# Master.net
KiCad netlist of a schematic drawn in Altium Designer
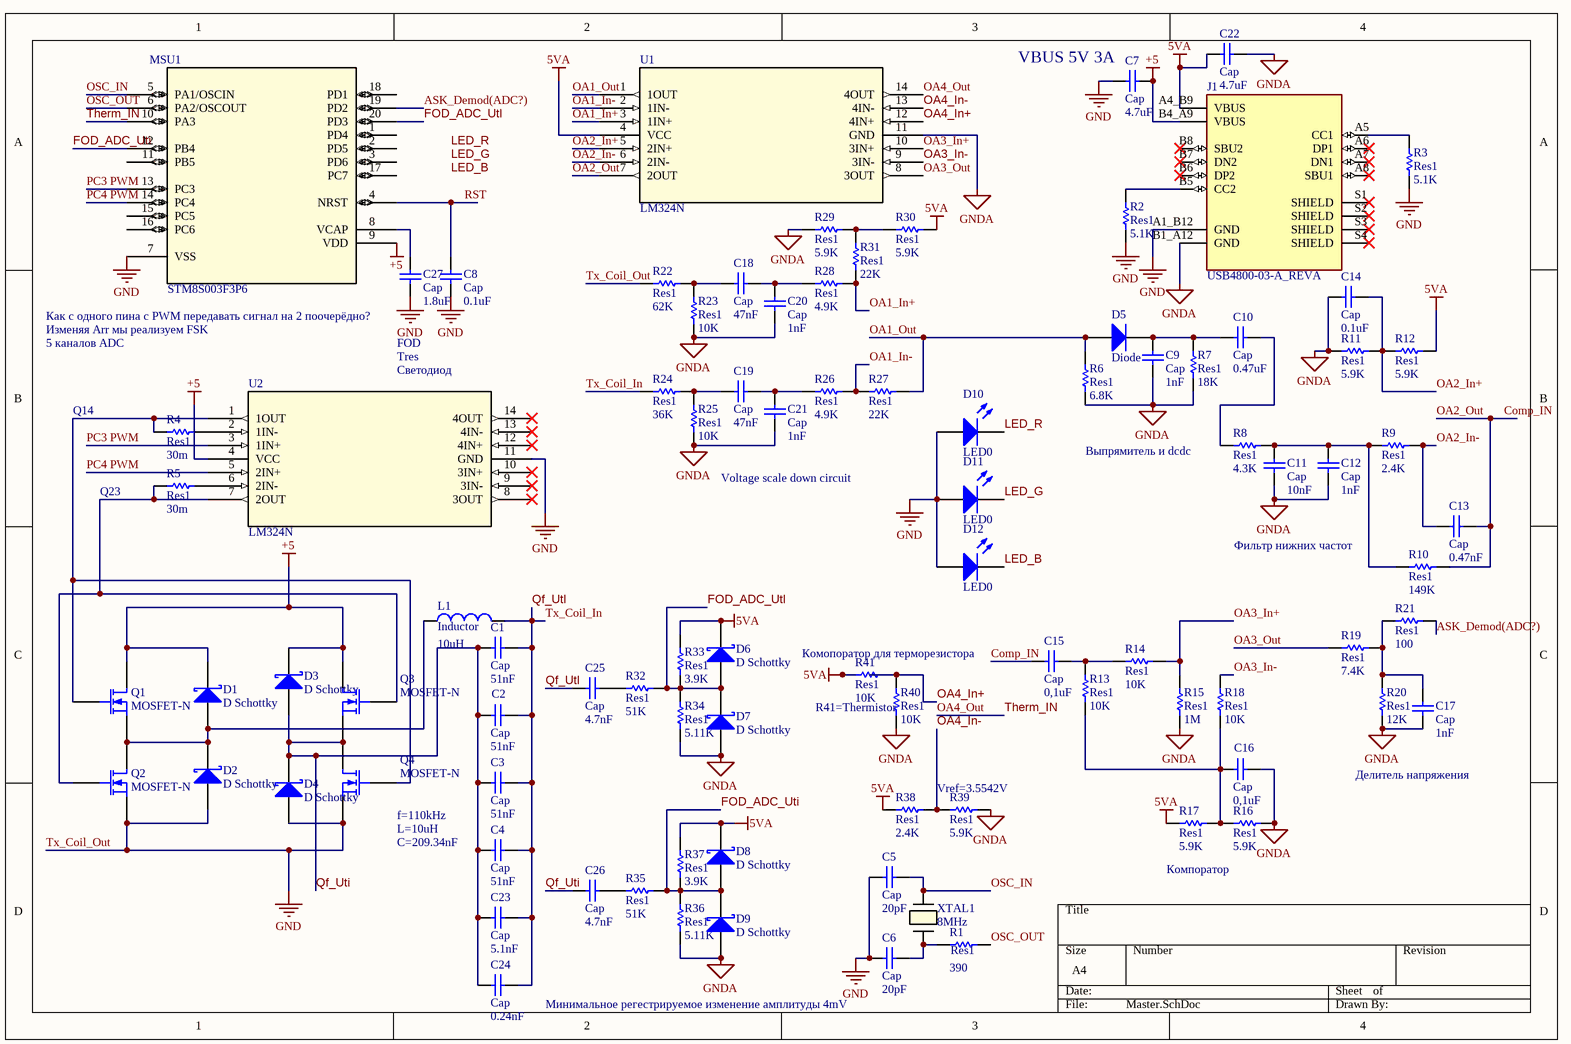
[diagram p0: Master.SchDoc]

(export (version "E")
  (design (tool "Eeschema 10.0.6"))
  (components
    (comp (ref "C1")
      (value "Cap")
      (footprint "RAD-0.3")
      (description "Capacitor")
      (fields (field (name "ALTIUM_VALUE") "51nF") (field (name "PUBLISHER") "Altium Limited"))
      (libsource (lib "Miscellaneous Devices") (part "Cap"))
    )
    (comp (ref "C2")
      (value "Cap")
      (footprint "RAD-0.3")
      (description "Capacitor")
      (fields (field (name "ALTIUM_VALUE") "51nF") (field (name "PUBLISHER") "Altium Limited"))
      (libsource (lib "Miscellaneous Devices") (part "Cap"))
    )
    (comp (ref "C3")
      (value "Cap")
      (footprint "RAD-0.3")
      (description "Capacitor")
      (fields (field (name "ALTIUM_VALUE") "51nF") (field (name "PUBLISHER") "Altium Limited"))
      (libsource (lib "Miscellaneous Devices") (part "Cap"))
    )
    (comp (ref "C4")
      (value "Cap")
      (footprint "RAD-0.3")
      (description "Capacitor")
      (fields (field (name "ALTIUM_VALUE") "51nF") (field (name "PUBLISHER") "Altium Limited"))
      (libsource (lib "Miscellaneous Devices") (part "Cap"))
    )
    (comp (ref "C5")
      (value "Cap")
      (footprint "RAD-0.3")
      (description "Capacitor")
      (fields (field (name "ALTIUM_VALUE") "20pF") (field (name "PUBLISHER") "Altium Limited"))
      (libsource (lib "Miscellaneous Devices") (part "Cap"))
    )
    (comp (ref "C6")
      (value "Cap")
      (footprint "RAD-0.3")
      (description "Capacitor")
      (fields (field (name "ALTIUM_VALUE") "20pF") (field (name "PUBLISHER") "Altium Limited"))
      (libsource (lib "Miscellaneous Devices") (part "Cap"))
    )
    (comp (ref "C7")
      (value "Cap")
      (footprint "RAD-0.3")
      (description "Capacitor")
      (fields (field (name "ALTIUM_VALUE") "4.7uF") (field (name "PUBLISHER") "Altium Limited"))
      (libsource (lib "Miscellaneous Devices") (part "Cap"))
    )
    (comp (ref "C8")
      (value "Cap")
      (footprint "RAD-0.3")
      (description "Capacitor")
      (fields (field (name "ALTIUM_VALUE") "0.1uF") (field (name "PUBLISHER") "Altium Limited"))
      (libsource (lib "Miscellaneous Devices") (part "Cap"))
    )
    (comp (ref "C9")
      (value "Cap")
      (footprint "RAD-0.3")
      (description "Capacitor")
      (fields (field (name "ALTIUM_VALUE") "1nF") (field (name "PUBLISHER") "Altium Limited"))
      (libsource (lib "Miscellaneous Devices") (part "Cap"))
    )
    (comp (ref "C10")
      (value "Cap")
      (footprint "RAD-0.3")
      (description "Capacitor")
      (fields (field (name "ALTIUM_VALUE") "0.47uF") (field (name "PUBLISHER") "Altium Limited"))
      (libsource (lib "Miscellaneous Devices") (part "Cap"))
    )
    (comp (ref "C11")
      (value "Cap")
      (footprint "RAD-0.3")
      (description "Capacitor")
      (fields (field (name "ALTIUM_VALUE") "10nF") (field (name "PUBLISHER") "Altium Limited"))
      (libsource (lib "Miscellaneous Devices") (part "Cap"))
    )
    (comp (ref "C12")
      (value "Cap")
      (footprint "RAD-0.3")
      (description "Capacitor")
      (fields (field (name "ALTIUM_VALUE") "1nF") (field (name "PUBLISHER") "Altium Limited"))
      (libsource (lib "Miscellaneous Devices") (part "Cap"))
    )
    (comp (ref "C13")
      (value "Cap")
      (footprint "RAD-0.3")
      (description "Capacitor")
      (fields (field (name "ALTIUM_VALUE") "0.47nF") (field (name "PUBLISHER") "Altium Limited"))
      (libsource (lib "Miscellaneous Devices") (part "Cap"))
    )
    (comp (ref "C14")
      (value "Cap")
      (footprint "RAD-0.3")
      (description "Capacitor")
      (fields (field (name "ALTIUM_VALUE") "0.1uF") (field (name "PUBLISHER") "Altium Limited"))
      (libsource (lib "Miscellaneous Devices") (part "Cap"))
    )
    (comp (ref "C15")
      (value "Cap")
      (footprint "RAD-0.3")
      (description "Capacitor")
      (fields (field (name "ALTIUM_VALUE") "0,1uF") (field (name "PUBLISHER") "Altium Limited"))
      (libsource (lib "Miscellaneous Devices") (part "Cap"))
    )
    (comp (ref "C16")
      (value "Cap")
      (footprint "RAD-0.3")
      (description "Capacitor")
      (fields (field (name "ALTIUM_VALUE") "0,1uF") (field (name "PUBLISHER") "Altium Limited"))
      (libsource (lib "Miscellaneous Devices") (part "Cap"))
    )
    (comp (ref "C17")
      (value "Cap")
      (footprint "RAD-0.3")
      (description "Capacitor")
      (fields (field (name "ALTIUM_VALUE") "1nF") (field (name "PUBLISHER") "Altium Limited"))
      (libsource (lib "Miscellaneous Devices") (part "Cap"))
    )
    (comp (ref "C18")
      (value "Cap")
      (footprint "RAD-0.3")
      (description "Capacitor")
      (fields (field (name "ALTIUM_VALUE") "47nF") (field (name "PUBLISHER") "Altium Limited"))
      (libsource (lib "Miscellaneous Devices") (part "Cap"))
    )
    (comp (ref "C19")
      (value "Cap")
      (footprint "RAD-0.3")
      (description "Capacitor")
      (fields (field (name "ALTIUM_VALUE") "47nF") (field (name "PUBLISHER") "Altium Limited"))
      (libsource (lib "Miscellaneous Devices") (part "Cap"))
    )
    (comp (ref "C20")
      (value "Cap")
      (footprint "RAD-0.3")
      (description "Capacitor")
      (fields (field (name "ALTIUM_VALUE") "1nF") (field (name "PUBLISHER") "Altium Limited"))
      (libsource (lib "Miscellaneous Devices") (part "Cap"))
    )
    (comp (ref "C21")
      (value "Cap")
      (footprint "RAD-0.3")
      (description "Capacitor")
      (fields (field (name "ALTIUM_VALUE") "1nF") (field (name "PUBLISHER") "Altium Limited"))
      (libsource (lib "Miscellaneous Devices") (part "Cap"))
    )
    (comp (ref "C22")
      (value "Cap")
      (footprint "RAD-0.3")
      (description "Capacitor")
      (fields (field (name "ALTIUM_VALUE") "4.7uF") (field (name "PUBLISHER") "Altium Limited"))
      (libsource (lib "Miscellaneous Devices") (part "Cap"))
    )
    (comp (ref "C23")
      (value "Cap")
      (footprint "RAD-0.3")
      (description "Capacitor")
      (fields (field (name "ALTIUM_VALUE") "5.1nF") (field (name "PUBLISHER") "Altium Limited"))
      (libsource (lib "Miscellaneous Devices") (part "Cap"))
    )
    (comp (ref "C24")
      (value "Cap")
      (footprint "RAD-0.3")
      (description "Capacitor")
      (fields (field (name "ALTIUM_VALUE") "0.24nF") (field (name "PUBLISHER") "Altium Limited"))
      (libsource (lib "Miscellaneous Devices") (part "Cap"))
    )
    (comp (ref "C25")
      (value "Cap")
      (footprint "RAD-0.3")
      (description "Capacitor")
      (fields (field (name "ALTIUM_VALUE") "4.7nF") (field (name "PUBLISHER") "Altium Limited"))
      (libsource (lib "Miscellaneous Devices") (part "Cap"))
    )
    (comp (ref "C26")
      (value "Cap")
      (footprint "RAD-0.3")
      (description "Capacitor")
      (fields (field (name "ALTIUM_VALUE") "4.7nF") (field (name "PUBLISHER") "Altium Limited"))
      (libsource (lib "Miscellaneous Devices") (part "Cap"))
    )
    (comp (ref "C27")
      (value "Cap")
      (footprint "RAD-0.3")
      (description "Capacitor")
      (fields (field (name "ALTIUM_VALUE") "1.8uF") (field (name "PUBLISHER") "Altium Limited"))
      (libsource (lib "Miscellaneous Devices") (part "Cap"))
    )
    (comp (ref "D1")
      (value "D Schottky")
      (footprint "SMB")
      (description "Schottky Diode")
      (fields (field (name "PUBLISHER") "Altium Limited"))
      (libsource (lib "Miscellaneous Devices") (part "D Schottky"))
    )
    (comp (ref "D2")
      (value "D Schottky")
      (footprint "SMB")
      (description "Schottky Diode")
      (fields (field (name "PUBLISHER") "Altium Limited"))
      (libsource (lib "Miscellaneous Devices") (part "D Schottky"))
    )
    (comp (ref "D3")
      (value "D Schottky")
      (footprint "SMB")
      (description "Schottky Diode")
      (fields (field (name "PUBLISHER") "Altium Limited"))
      (libsource (lib "Miscellaneous Devices") (part "D Schottky"))
    )
    (comp (ref "D4")
      (value "D Schottky")
      (footprint "SMB")
      (description "Schottky Diode")
      (fields (field (name "PUBLISHER") "Altium Limited"))
      (libsource (lib "Miscellaneous Devices") (part "D Schottky"))
    )
    (comp (ref "D5")
      (value "Diode")
      (footprint "SMC")
      (description "Default Diode")
      (fields (field (name "PUBLISHER") "Altium Limited"))
      (libsource (lib "Miscellaneous Devices") (part "Diode"))
    )
    (comp (ref "D6")
      (value "D Schottky")
      (footprint "SMB")
      (description "Schottky Diode")
      (fields (field (name "PUBLISHER") "Altium Limited"))
      (libsource (lib "Miscellaneous Devices") (part "D Schottky"))
    )
    (comp (ref "D7")
      (value "D Schottky")
      (footprint "SMB")
      (description "Schottky Diode")
      (fields (field (name "PUBLISHER") "Altium Limited"))
      (libsource (lib "Miscellaneous Devices") (part "D Schottky"))
    )
    (comp (ref "D8")
      (value "D Schottky")
      (footprint "SMB")
      (description "Schottky Diode")
      (fields (field (name "PUBLISHER") "Altium Limited"))
      (libsource (lib "Miscellaneous Devices") (part "D Schottky"))
    )
    (comp (ref "D9")
      (value "D Schottky")
      (footprint "SMB")
      (description "Schottky Diode")
      (fields (field (name "PUBLISHER") "Altium Limited"))
      (libsource (lib "Miscellaneous Devices") (part "D Schottky"))
    )
    (comp (ref "D10")
      (value "LED0")
      (footprint "LED-0")
      (description "Typical INFRARED GaAs LED")
      (fields (field (name "PUBLISHER") "Altium Limited"))
      (libsource (lib "Miscellaneous Devices") (part "LED0"))
    )
    (comp (ref "D11")
      (value "LED0")
      (footprint "LED-0")
      (description "Typical INFRARED GaAs LED")
      (fields (field (name "PUBLISHER") "Altium Limited"))
      (libsource (lib "Miscellaneous Devices") (part "LED0"))
    )
    (comp (ref "D12")
      (value "LED0")
      (footprint "LED-0")
      (description "Typical INFRARED GaAs LED")
      (fields (field (name "PUBLISHER") "Altium Limited"))
      (libsource (lib "Miscellaneous Devices") (part "LED0"))
    )
    (comp (ref "J1")
      (value "USB4800-03-A_REVA")
      (footprint "GCT_USB4800-03-A_REVA")
      (fields (field (name "MP") "USB4800-03-A") (field (name "MF") "Global Connector Technology"))
      (libsource (lib "USB4800-03-A_REVA") (part "USB4800-03-A_REVA"))
    )
    (comp (ref "L1")
      (value "Inductor")
      (footprint "0402-A")
      (fields (field (name "ALTIUM_VALUE") "10uH") (field (name "PUBLISHER") "Altium Limited"))
      (libsource (lib "Miscellaneous Devices") (part "Inductor"))
    )
    (comp (ref "MSU1")
      (value "STM8S003F3P6")
      (footprint "TSSOP20")
      (description "No Description Available")
      (libsource (lib "STM8S003F3P6") (part "STM8S003F3P6"))
    )
    (comp (ref "Q1")
      (value "MOSFET-N")
      (footprint "E3")
      (description "N-Channel MOSFET")
      (fields (field (name "PUBLISHER") "Altium Limited"))
      (libsource (lib "Miscellaneous Devices") (part "MOSFET-N"))
    )
    (comp (ref "Q2")
      (value "MOSFET-N")
      (footprint "E3")
      (description "N-Channel MOSFET")
      (fields (field (name "PUBLISHER") "Altium Limited"))
      (libsource (lib "Miscellaneous Devices") (part "MOSFET-N"))
    )
    (comp (ref "Q3")
      (value "MOSFET-N")
      (footprint "E3")
      (description "N-Channel MOSFET")
      (fields (field (name "PUBLISHER") "Altium Limited"))
      (libsource (lib "Miscellaneous Devices") (part "MOSFET-N"))
    )
    (comp (ref "Q4")
      (value "MOSFET-N")
      (footprint "E3")
      (description "N-Channel MOSFET")
      (fields (field (name "PUBLISHER") "Altium Limited"))
      (libsource (lib "Miscellaneous Devices") (part "MOSFET-N"))
    )
    (comp (ref "R1")
      (value "Res1")
      (footprint "AXIAL-0.3")
      (description "Resistor")
      (fields (field (name "ALTIUM_VALUE") "390") (field (name "PUBLISHER") "Altium Limited"))
      (libsource (lib "Miscellaneous Devices") (part "Res1"))
    )
    (comp (ref "R2")
      (value "Res1")
      (footprint "AXIAL-0.3")
      (description "Resistor")
      (fields (field (name "ALTIUM_VALUE") "5.1K") (field (name "PUBLISHER") "Altium Limited"))
      (libsource (lib "Miscellaneous Devices") (part "Res1"))
    )
    (comp (ref "R3")
      (value "Res1")
      (footprint "AXIAL-0.3")
      (description "Resistor")
      (fields (field (name "ALTIUM_VALUE") "5.1K") (field (name "PUBLISHER") "Altium Limited"))
      (libsource (lib "Miscellaneous Devices") (part "Res1"))
    )
    (comp (ref "R4")
      (value "Res1")
      (footprint "AXIAL-0.3")
      (description "Resistor")
      (fields (field (name "ALTIUM_VALUE") "30m") (field (name "PUBLISHER") "Altium Limited"))
      (libsource (lib "Miscellaneous Devices") (part "Res1"))
    )
    (comp (ref "R5")
      (value "Res1")
      (footprint "AXIAL-0.3")
      (description "Resistor")
      (fields (field (name "ALTIUM_VALUE") "30m") (field (name "PUBLISHER") "Altium Limited"))
      (libsource (lib "Miscellaneous Devices") (part "Res1"))
    )
    (comp (ref "R6")
      (value "Res1")
      (footprint "AXIAL-0.3")
      (description "Resistor")
      (fields (field (name "ALTIUM_VALUE") "6.8K") (field (name "PUBLISHER") "Altium Limited"))
      (libsource (lib "Miscellaneous Devices") (part "Res1"))
    )
    (comp (ref "R7")
      (value "Res1")
      (footprint "AXIAL-0.3")
      (description "Resistor")
      (fields (field (name "ALTIUM_VALUE") "18K") (field (name "PUBLISHER") "Altium Limited"))
      (libsource (lib "Miscellaneous Devices") (part "Res1"))
    )
    (comp (ref "R8")
      (value "Res1")
      (footprint "AXIAL-0.3")
      (description "Resistor")
      (fields (field (name "ALTIUM_VALUE") "4.3K") (field (name "PUBLISHER") "Altium Limited"))
      (libsource (lib "Miscellaneous Devices") (part "Res1"))
    )
    (comp (ref "R9")
      (value "Res1")
      (footprint "AXIAL-0.3")
      (description "Resistor")
      (fields (field (name "ALTIUM_VALUE") "2.4K") (field (name "PUBLISHER") "Altium Limited"))
      (libsource (lib "Miscellaneous Devices") (part "Res1"))
    )
    (comp (ref "R10")
      (value "Res1")
      (footprint "AXIAL-0.3")
      (description "Resistor")
      (fields (field (name "ALTIUM_VALUE") "149K") (field (name "PUBLISHER") "Altium Limited"))
      (libsource (lib "Miscellaneous Devices") (part "Res1"))
    )
    (comp (ref "R11")
      (value "Res1")
      (footprint "AXIAL-0.3")
      (description "Resistor")
      (fields (field (name "ALTIUM_VALUE") "5.9K") (field (name "PUBLISHER") "Altium Limited"))
      (libsource (lib "Miscellaneous Devices") (part "Res1"))
    )
    (comp (ref "R12")
      (value "Res1")
      (footprint "AXIAL-0.3")
      (description "Resistor")
      (fields (field (name "ALTIUM_VALUE") "5.9K") (field (name "PUBLISHER") "Altium Limited"))
      (libsource (lib "Miscellaneous Devices") (part "Res1"))
    )
    (comp (ref "R13")
      (value "Res1")
      (footprint "AXIAL-0.3")
      (description "Resistor")
      (fields (field (name "ALTIUM_VALUE") "10K") (field (name "PUBLISHER") "Altium Limited"))
      (libsource (lib "Miscellaneous Devices") (part "Res1"))
    )
    (comp (ref "R14")
      (value "Res1")
      (footprint "AXIAL-0.3")
      (description "Resistor")
      (fields (field (name "ALTIUM_VALUE") "10K") (field (name "PUBLISHER") "Altium Limited"))
      (libsource (lib "Miscellaneous Devices") (part "Res1"))
    )
    (comp (ref "R15")
      (value "Res1")
      (footprint "AXIAL-0.3")
      (description "Resistor")
      (fields (field (name "ALTIUM_VALUE") "1M") (field (name "PUBLISHER") "Altium Limited"))
      (libsource (lib "Miscellaneous Devices") (part "Res1"))
    )
    (comp (ref "R16")
      (value "Res1")
      (footprint "AXIAL-0.3")
      (description "Resistor")
      (fields (field (name "ALTIUM_VALUE") "5.9K") (field (name "PUBLISHER") "Altium Limited"))
      (libsource (lib "Miscellaneous Devices") (part "Res1"))
    )
    (comp (ref "R17")
      (value "Res1")
      (footprint "AXIAL-0.3")
      (description "Resistor")
      (fields (field (name "ALTIUM_VALUE") "5.9K") (field (name "PUBLISHER") "Altium Limited"))
      (libsource (lib "Miscellaneous Devices") (part "Res1"))
    )
    (comp (ref "R18")
      (value "Res1")
      (footprint "AXIAL-0.3")
      (description "Resistor")
      (fields (field (name "ALTIUM_VALUE") "10K") (field (name "PUBLISHER") "Altium Limited"))
      (libsource (lib "Miscellaneous Devices") (part "Res1"))
    )
    (comp (ref "R19")
      (value "Res1")
      (footprint "AXIAL-0.3")
      (description "Resistor")
      (fields (field (name "ALTIUM_VALUE") "7.4K") (field (name "PUBLISHER") "Altium Limited"))
      (libsource (lib "Miscellaneous Devices") (part "Res1"))
    )
    (comp (ref "R20")
      (value "Res1")
      (footprint "AXIAL-0.3")
      (description "Resistor")
      (fields (field (name "ALTIUM_VALUE") "12K") (field (name "PUBLISHER") "Altium Limited"))
      (libsource (lib "Miscellaneous Devices") (part "Res1"))
    )
    (comp (ref "R21")
      (value "Res1")
      (footprint "AXIAL-0.3")
      (description "Resistor")
      (fields (field (name "ALTIUM_VALUE") "100") (field (name "PUBLISHER") "Altium Limited"))
      (libsource (lib "Miscellaneous Devices") (part "Res1"))
    )
    (comp (ref "R22")
      (value "Res1")
      (footprint "AXIAL-0.3")
      (description "Resistor")
      (fields (field (name "ALTIUM_VALUE") "62K") (field (name "PUBLISHER") "Altium Limited"))
      (libsource (lib "Miscellaneous Devices") (part "Res1"))
    )
    (comp (ref "R23")
      (value "Res1")
      (footprint "AXIAL-0.3")
      (description "Resistor")
      (fields (field (name "ALTIUM_VALUE") "10K") (field (name "PUBLISHER") "Altium Limited"))
      (libsource (lib "Miscellaneous Devices") (part "Res1"))
    )
    (comp (ref "R24")
      (value "Res1")
      (footprint "AXIAL-0.3")
      (description "Resistor")
      (fields (field (name "ALTIUM_VALUE") "36K") (field (name "PUBLISHER") "Altium Limited"))
      (libsource (lib "Miscellaneous Devices") (part "Res1"))
    )
    (comp (ref "R25")
      (value "Res1")
      (footprint "AXIAL-0.3")
      (description "Resistor")
      (fields (field (name "ALTIUM_VALUE") "10K") (field (name "PUBLISHER") "Altium Limited"))
      (libsource (lib "Miscellaneous Devices") (part "Res1"))
    )
    (comp (ref "R26")
      (value "Res1")
      (footprint "AXIAL-0.3")
      (description "Resistor")
      (fields (field (name "ALTIUM_VALUE") "4.9K") (field (name "PUBLISHER") "Altium Limited"))
      (libsource (lib "Miscellaneous Devices") (part "Res1"))
    )
    (comp (ref "R27")
      (value "Res1")
      (footprint "AXIAL-0.3")
      (description "Resistor")
      (fields (field (name "ALTIUM_VALUE") "22K") (field (name "PUBLISHER") "Altium Limited"))
      (libsource (lib "Miscellaneous Devices") (part "Res1"))
    )
    (comp (ref "R28")
      (value "Res1")
      (footprint "AXIAL-0.3")
      (description "Resistor")
      (fields (field (name "ALTIUM_VALUE") "4.9K") (field (name "PUBLISHER") "Altium Limited"))
      (libsource (lib "Miscellaneous Devices") (part "Res1"))
    )
    (comp (ref "R29")
      (value "Res1")
      (footprint "AXIAL-0.3")
      (description "Resistor")
      (fields (field (name "ALTIUM_VALUE") "5.9K") (field (name "PUBLISHER") "Altium Limited"))
      (libsource (lib "Miscellaneous Devices") (part "Res1"))
    )
    (comp (ref "R30")
      (value "Res1")
      (footprint "AXIAL-0.3")
      (description "Resistor")
      (fields (field (name "ALTIUM_VALUE") "5.9K") (field (name "PUBLISHER") "Altium Limited"))
      (libsource (lib "Miscellaneous Devices") (part "Res1"))
    )
    (comp (ref "R31")
      (value "Res1")
      (footprint "AXIAL-0.3")
      (description "Resistor")
      (fields (field (name "ALTIUM_VALUE") "22K") (field (name "PUBLISHER") "Altium Limited"))
      (libsource (lib "Miscellaneous Devices") (part "Res1"))
    )
    (comp (ref "R32")
      (value "Res1")
      (footprint "AXIAL-0.3")
      (description "Resistor")
      (fields (field (name "ALTIUM_VALUE") "51K") (field (name "PUBLISHER") "Altium Limited"))
      (libsource (lib "Miscellaneous Devices") (part "Res1"))
    )
    (comp (ref "R33")
      (value "Res1")
      (footprint "AXIAL-0.3")
      (description "Resistor")
      (fields (field (name "ALTIUM_VALUE") "3.9K") (field (name "PUBLISHER") "Altium Limited"))
      (libsource (lib "Miscellaneous Devices") (part "Res1"))
    )
    (comp (ref "R34")
      (value "Res1")
      (footprint "AXIAL-0.3")
      (description "Resistor")
      (fields (field (name "ALTIUM_VALUE") "5.11K") (field (name "PUBLISHER") "Altium Limited"))
      (libsource (lib "Miscellaneous Devices") (part "Res1"))
    )
    (comp (ref "R35")
      (value "Res1")
      (footprint "AXIAL-0.3")
      (description "Resistor")
      (fields (field (name "ALTIUM_VALUE") "51K") (field (name "PUBLISHER") "Altium Limited"))
      (libsource (lib "Miscellaneous Devices") (part "Res1"))
    )
    (comp (ref "R36")
      (value "Res1")
      (footprint "AXIAL-0.3")
      (description "Resistor")
      (fields (field (name "ALTIUM_VALUE") "5.11K") (field (name "PUBLISHER") "Altium Limited"))
      (libsource (lib "Miscellaneous Devices") (part "Res1"))
    )
    (comp (ref "R37")
      (value "Res1")
      (footprint "AXIAL-0.3")
      (description "Resistor")
      (fields (field (name "ALTIUM_VALUE") "3.9K") (field (name "PUBLISHER") "Altium Limited"))
      (libsource (lib "Miscellaneous Devices") (part "Res1"))
    )
    (comp (ref "R38")
      (value "Res1")
      (footprint "AXIAL-0.3")
      (description "Resistor")
      (fields (field (name "ALTIUM_VALUE") "2.4K") (field (name "PUBLISHER") "Altium Limited"))
      (libsource (lib "Miscellaneous Devices") (part "Res1"))
    )
    (comp (ref "R39")
      (value "Res1")
      (footprint "AXIAL-0.3")
      (description "Resistor")
      (fields (field (name "ALTIUM_VALUE") "5.9K") (field (name "PUBLISHER") "Altium Limited"))
      (libsource (lib "Miscellaneous Devices") (part "Res1"))
    )
    (comp (ref "R40")
      (value "Res1")
      (footprint "AXIAL-0.3")
      (description "Resistor")
      (fields (field (name "ALTIUM_VALUE") "10K") (field (name "PUBLISHER") "Altium Limited"))
      (libsource (lib "Miscellaneous Devices") (part "Res1"))
    )
    (comp (ref "R41")
      (value "Res1")
      (footprint "AXIAL-0.3")
      (description "Resistor")
      (fields (field (name "ALTIUM_VALUE") "10K") (field (name "PUBLISHER") "Altium Limited"))
      (libsource (lib "Miscellaneous Devices") (part "Res1"))
    )
    (comp (ref "U1")
      (value "LM324N")
      (footprint "N14")
      (description "No Description Available")
      (libsource (lib "LM324N") (part "LM324N"))
    )
    (comp (ref "U2")
      (value "LM324N")
      (footprint "N14")
      (description "No Description Available")
      (libsource (lib "LM324N") (part "LM324N"))
    )
    (comp (ref "XTAL1")
      (value "8MHz")
      (footprint "CRYSTAL_ECS-80-18-5PX-TR_ECS")
      (description "No Description Available")
      (libsource (lib "ECS-80-18-5PX-TR") (part "ECS-80-18-5PX-TR"))
    )
  )
  (nets
    (net (code "1") (name "+5") (class "Default")
      (node (ref "C7") (pin "1") (pinfunction "1_1") (pintype "passive"))
      (node (ref "D1") (pin "2") (pinfunction "K_2") (pintype "passive"))
      (node (ref "D3") (pin "2") (pinfunction "K_2") (pintype "passive"))
      (node (ref "J1") (pin "B4_A9") (pinfunction "VBUS_B4_A9") (pintype "power_in"))
      (node (ref "MSU1") (pin "9") (pinfunction "VDD_9") (pintype "power_in"))
      (node (ref "Q1") (pin "1") (pinfunction "D_1") (pintype "passive"))
      (node (ref "Q3") (pin "1") (pinfunction "D_1") (pintype "passive"))
      (node (ref "U2") (pin "4") (pinfunction "VCC_4") (pintype "power_in"))
    )
    (net (code "2") (name "/ASK_Demod(ADC?)") (class "Default")
      (node (ref "MSU1") (pin "19") (pinfunction "PD2_19") (pintype "bidirectional"))
      (node (ref "R21") (pin "2") (pinfunction "2_2") (pintype "passive"))
    )
    (net (code "3") (name "/Comp_IN") (class "Default")
      (node (ref "C13") (pin "2") (pinfunction "2_2") (pintype "passive"))
      (node (ref "C15") (pin "1") (pinfunction "1_1") (pintype "passive"))
      (node (ref "R10") (pin "2") (pinfunction "2_2") (pintype "passive"))
      (node (ref "U1") (pin "7") (pinfunction "2OUT_7") (pintype "output"))
    )
    (net (code "4") (name "/FOD_ADC_Uti") (class "Default")
      (node (ref "D8") (pin "1") (pinfunction "A_1") (pintype "passive"))
      (node (ref "D9") (pin "2") (pinfunction "K_2") (pintype "passive"))
      (node (ref "MSU1") (pin "12") (pinfunction "PB4_12") (pintype "bidirectional"))
      (node (ref "R35") (pin "2") (pinfunction "2_2") (pintype "passive"))
      (node (ref "R36") (pin "2") (pinfunction "2_2") (pintype "passive"))
      (node (ref "R37") (pin "1") (pinfunction "1_1") (pintype "passive"))
    )
    (net (code "5") (name "/FOD_ADC_Utl") (class "Default")
      (node (ref "D6") (pin "1") (pinfunction "A_1") (pintype "passive"))
      (node (ref "D7") (pin "2") (pinfunction "K_2") (pintype "passive"))
      (node (ref "MSU1") (pin "20") (pinfunction "PD3_20") (pintype "bidirectional"))
      (node (ref "R32") (pin "1") (pinfunction "1_1") (pintype "passive"))
      (node (ref "R33") (pin "2") (pinfunction "2_2") (pintype "passive"))
      (node (ref "R34") (pin "2") (pinfunction "2_2") (pintype "passive"))
    )
    (net (code "6") (name "/LED_B") (class "Default")
      (node (ref "D12") (pin "2") (pinfunction "K_2") (pintype "passive"))
    )
    (net (code "7") (name "/LED_G") (class "Default")
      (node (ref "D11") (pin "2") (pinfunction "K_2") (pintype "passive"))
    )
    (net (code "8") (name "/LED_R") (class "Default")
      (node (ref "D10") (pin "2") (pinfunction "K_2") (pintype "passive"))
    )
    (net (code "9") (name "/OA1_In+") (class "Default")
      (node (ref "R28") (pin "1") (pinfunction "1_1") (pintype "passive"))
      (node (ref "R31") (pin "2") (pinfunction "2_2") (pintype "passive"))
      (node (ref "U1") (pin "3") (pinfunction "1IN+_3") (pintype "input"))
    )
    (net (code "10") (name "/OA1_In-") (class "Default")
      (node (ref "R26") (pin "2") (pinfunction "2_2") (pintype "passive"))
      (node (ref "R27") (pin "1") (pinfunction "1_1") (pintype "passive"))
      (node (ref "U1") (pin "2") (pinfunction "1IN-_2") (pintype "input"))
    )
    (net (code "11") (name "/OA1_Out") (class "Default")
      (node (ref "D5") (pin "1") (pinfunction "A_1") (pintype "passive"))
      (node (ref "R27") (pin "2") (pinfunction "2_2") (pintype "passive"))
      (node (ref "R6") (pin "1") (pinfunction "1_1") (pintype "passive"))
      (node (ref "U1") (pin "1") (pinfunction "1OUT_1") (pintype "output"))
    )
    (net (code "12") (name "/OA2_In+") (class "Default")
      (node (ref "C14") (pin "2") (pinfunction "2_2") (pintype "passive"))
      (node (ref "R11") (pin "2") (pinfunction "2_2") (pintype "passive"))
      (node (ref "R12") (pin "1") (pinfunction "1_1") (pintype "passive"))
      (node (ref "U1") (pin "5") (pinfunction "2IN+_5") (pintype "input"))
    )
    (net (code "13") (name "/OA2_In-") (class "Default")
      (node (ref "C13") (pin "1") (pinfunction "1_1") (pintype "passive"))
      (node (ref "R9") (pin "2") (pinfunction "2_2") (pintype "passive"))
      (node (ref "U1") (pin "6") (pinfunction "2IN-_6") (pintype "input"))
    )
    (net (code "14") (name "/OA3_In+") (class "Default")
      (node (ref "R14") (pin "2") (pinfunction "2_2") (pintype "passive"))
      (node (ref "R15") (pin "1") (pinfunction "1_1") (pintype "passive"))
      (node (ref "U1") (pin "10") (pinfunction "3IN+_10") (pintype "input"))
    )
    (net (code "15") (name "/OA3_In-") (class "Default")
      (node (ref "R18") (pin "2") (pinfunction "2_2") (pintype "passive"))
      (node (ref "U1") (pin "9") (pinfunction "3IN-_9") (pintype "input"))
    )
    (net (code "16") (name "/OA3_Out") (class "Default")
      (node (ref "R19") (pin "1") (pinfunction "1_1") (pintype "passive"))
      (node (ref "U1") (pin "8") (pinfunction "3OUT_8") (pintype "output"))
    )
    (net (code "17") (name "/OA4_In+") (class "Default")
      (node (ref "R40") (pin "2") (pinfunction "2_2") (pintype "passive"))
      (node (ref "R41") (pin "2") (pinfunction "2_2") (pintype "passive"))
      (node (ref "U1") (pin "12") (pinfunction "4IN+_12") (pintype "input"))
    )
    (net (code "18") (name "/OA4_In-") (class "Default")
      (node (ref "R38") (pin "2") (pinfunction "2_2") (pintype "passive"))
      (node (ref "R39") (pin "1") (pinfunction "1_1") (pintype "passive"))
      (node (ref "U1") (pin "13") (pinfunction "4IN-_13") (pintype "input"))
    )
    (net (code "19") (name "/OA4_Out") (class "Default")
      (node (ref "MSU1") (pin "10") (pinfunction "PA3_10") (pintype "bidirectional"))
      (node (ref "U1") (pin "14") (pinfunction "4OUT_14") (pintype "output"))
    )
    (net (code "20") (name "/OSC_IN") (class "Default")
      (node (ref "C5") (pin "1") (pinfunction "1_1") (pintype "passive"))
      (node (ref "MSU1") (pin "5") (pinfunction "PA1/OSCIN_5") (pintype "bidirectional"))
      (node (ref "XTAL1") (pin "1") (pinfunction "1_1") (pintype "passive"))
    )
    (net (code "21") (name "/OSC_OUT") (class "Default")
      (node (ref "MSU1") (pin "6") (pinfunction "PA2/OSCOUT_6") (pintype "bidirectional"))
      (node (ref "R1") (pin "2") (pinfunction "2_2") (pintype "passive"))
    )
    (net (code "22") (name "/PC3 PWM") (class "Default")
      (node (ref "MSU1") (pin "13") (pinfunction "PC3_13") (pintype "bidirectional"))
      (node (ref "U2") (pin "3") (pinfunction "1IN+_3") (pintype "input"))
    )
    (net (code "23") (name "/PC4 PWM") (class "Default")
      (node (ref "MSU1") (pin "14") (pinfunction "PC4_14") (pintype "bidirectional"))
      (node (ref "U2") (pin "5") (pinfunction "2IN+_5") (pintype "input"))
    )
    (net (code "24") (name "/Qf_Uti") (class "Default")
      (node (ref "C1") (pin "1") (pinfunction "1_1") (pintype "passive"))
      (node (ref "C2") (pin "1") (pinfunction "1_1") (pintype "passive"))
      (node (ref "C23") (pin "2") (pinfunction "2_2") (pintype "passive"))
      (node (ref "C24") (pin "1") (pinfunction "1_1") (pintype "passive"))
      (node (ref "C26") (pin "1") (pinfunction "1_1") (pintype "passive"))
      (node (ref "C3") (pin "1") (pinfunction "1_1") (pintype "passive"))
      (node (ref "C4") (pin "1") (pinfunction "1_1") (pintype "passive"))
      (node (ref "D3") (pin "1") (pinfunction "A_1") (pintype "passive"))
      (node (ref "D4") (pin "2") (pinfunction "K_2") (pintype "passive"))
      (node (ref "Q3") (pin "3") (pinfunction "S_3") (pintype "passive"))
      (node (ref "Q4") (pin "1") (pinfunction "D_1") (pintype "passive"))
    )
    (net (code "25") (name "/Qf_Utl") (class "Default")
      (node (ref "C1") (pin "2") (pinfunction "2_2") (pintype "passive"))
      (node (ref "C2") (pin "2") (pinfunction "2_2") (pintype "passive"))
      (node (ref "C23") (pin "1") (pinfunction "1_1") (pintype "passive"))
      (node (ref "C24") (pin "2") (pinfunction "2_2") (pintype "passive"))
      (node (ref "C25") (pin "1") (pinfunction "1_1") (pintype "passive"))
      (node (ref "C3") (pin "2") (pinfunction "2_2") (pintype "passive"))
      (node (ref "C4") (pin "2") (pinfunction "2_2") (pintype "passive"))
      (node (ref "L1") (pin "2") (pinfunction "2_2") (pintype "passive"))
      (node (ref "R24") (pin "1") (pinfunction "1_1") (pintype "passive"))
    )
    (net (code "26") (name "/RST") (class "Default")
      (node (ref "C8") (pin "2") (pinfunction "2_2") (pintype "passive"))
      (node (ref "MSU1") (pin "4") (pinfunction "NRST_4") (pintype "bidirectional"))
    )
    (net (code "27") (name "5VA") (class "Default")
      (node (ref "C22") (pin "1") (pinfunction "1_1") (pintype "passive"))
      (node (ref "D6") (pin "2") (pinfunction "K_2") (pintype "passive"))
      (node (ref "D8") (pin "2") (pinfunction "K_2") (pintype "passive"))
      (node (ref "J1") (pin "A4_B9") (pinfunction "VBUS_A4_B9") (pintype "power_in"))
      (node (ref "R12") (pin "2") (pinfunction "2_2") (pintype "passive"))
      (node (ref "R17") (pin "1") (pinfunction "1_1") (pintype "passive"))
      (node (ref "R30") (pin "2") (pinfunction "2_2") (pintype "passive"))
      (node (ref "R33") (pin "1") (pinfunction "1_1") (pintype "passive"))
      (node (ref "R37") (pin "2") (pinfunction "2_2") (pintype "passive"))
      (node (ref "R38") (pin "1") (pinfunction "1_1") (pintype "passive"))
      (node (ref "R41") (pin "1") (pinfunction "1_1") (pintype "passive"))
      (node (ref "U1") (pin "4") (pinfunction "VCC_4") (pintype "power_in"))
    )
    (net (code "28") (name "GND") (class "Default")
      (node (ref "C27") (pin "2") (pinfunction "2_2") (pintype "passive"))
      (node (ref "C5") (pin "2") (pinfunction "2_2") (pintype "passive"))
      (node (ref "C6") (pin "2") (pinfunction "2_2") (pintype "passive"))
      (node (ref "C7") (pin "2") (pinfunction "2_2") (pintype "passive"))
      (node (ref "C8") (pin "1") (pinfunction "1_1") (pintype "passive"))
      (node (ref "D10") (pin "1") (pinfunction "A_1") (pintype "passive"))
      (node (ref "D11") (pin "1") (pinfunction "A_1") (pintype "passive"))
      (node (ref "D12") (pin "1") (pinfunction "A_1") (pintype "passive"))
      (node (ref "D2") (pin "1") (pinfunction "A_1") (pintype "passive"))
      (node (ref "D4") (pin "1") (pinfunction "A_1") (pintype "passive"))
      (node (ref "J1") (pin "A1_B12") (pinfunction "GND_A1_B12") (pintype "power_in"))
      (node (ref "MSU1") (pin "7") (pinfunction "VSS_7") (pintype "power_in"))
      (node (ref "Q2") (pin "3") (pinfunction "S_3") (pintype "passive"))
      (node (ref "Q4") (pin "3") (pinfunction "S_3") (pintype "passive"))
      (node (ref "R2") (pin "2") (pinfunction "2_2") (pintype "passive"))
      (node (ref "R22") (pin "2") (pinfunction "2_2") (pintype "passive"))
      (node (ref "R3") (pin "2") (pinfunction "2_2") (pintype "passive"))
      (node (ref "U2") (pin "11") (pinfunction "GND_11") (pintype "power_in"))
    )
    (net (code "29") (name "GNDA") (class "Default")
      (node (ref "C11") (pin "1") (pinfunction "1_1") (pintype "passive"))
      (node (ref "C12") (pin "2") (pinfunction "2_2") (pintype "passive"))
      (node (ref "C14") (pin "1") (pinfunction "1_1") (pintype "passive"))
      (node (ref "C16") (pin "2") (pinfunction "2_2") (pintype "passive"))
      (node (ref "C17") (pin "2") (pinfunction "2_2") (pintype "passive"))
      (node (ref "C20") (pin "1") (pinfunction "1_1") (pintype "passive"))
      (node (ref "C21") (pin "2") (pinfunction "2_2") (pintype "passive"))
      (node (ref "C22") (pin "2") (pinfunction "2_2") (pintype "passive"))
      (node (ref "C9") (pin "2") (pinfunction "2_2") (pintype "passive"))
      (node (ref "D7") (pin "1") (pinfunction "A_1") (pintype "passive"))
      (node (ref "D9") (pin "1") (pinfunction "A_1") (pintype "passive"))
      (node (ref "J1") (pin "B1_A12") (pinfunction "GND_B1_A12") (pintype "power_in"))
      (node (ref "R11") (pin "1") (pinfunction "1_1") (pintype "passive"))
      (node (ref "R15") (pin "2") (pinfunction "2_2") (pintype "passive"))
      (node (ref "R16") (pin "2") (pinfunction "2_2") (pintype "passive"))
      (node (ref "R20") (pin "2") (pinfunction "2_2") (pintype "passive"))
      (node (ref "R23") (pin "2") (pinfunction "2_2") (pintype "passive"))
      (node (ref "R25") (pin "1") (pinfunction "1_1") (pintype "passive"))
      (node (ref "R29") (pin "2") (pinfunction "2_2") (pintype "passive"))
      (node (ref "R34") (pin "1") (pinfunction "1_1") (pintype "passive"))
      (node (ref "R36") (pin "1") (pinfunction "1_1") (pintype "passive"))
      (node (ref "R39") (pin "2") (pinfunction "2_2") (pintype "passive"))
      (node (ref "R40") (pin "1") (pinfunction "1_1") (pintype "passive"))
      (node (ref "R6") (pin "2") (pinfunction "2_2") (pintype "passive"))
      (node (ref "R7") (pin "2") (pinfunction "2_2") (pintype "passive"))
      (node (ref "U1") (pin "11") (pinfunction "GND_11") (pintype "power_in"))
    )
    (net (code "30") (name "Net-(C6-Pad1)") (class "Default")
      (node (ref "C6") (pin "1") (pinfunction "1_1") (pintype "passive"))
      (node (ref "R1") (pin "1") (pinfunction "1_1") (pintype "passive"))
      (node (ref "XTAL1") (pin "2") (pinfunction "2_2") (pintype "passive"))
    )
    (net (code "31") (name "Net-(C10-Pad2)") (class "Default")
      (node (ref "C10") (pin "2") (pinfunction "2_2") (pintype "passive"))
      (node (ref "R8") (pin "2") (pinfunction "2_2") (pintype "passive"))
    )
    (net (code "32") (name "Net-(C11-Pad2)") (class "Default")
      (node (ref "C11") (pin "2") (pinfunction "2_2") (pintype "passive"))
      (node (ref "C12") (pin "1") (pinfunction "1_1") (pintype "passive"))
      (node (ref "R10") (pin "1") (pinfunction "1_1") (pintype "passive"))
      (node (ref "R8") (pin "1") (pinfunction "1_1") (pintype "passive"))
      (node (ref "R9") (pin "1") (pinfunction "1_1") (pintype "passive"))
    )
    (net (code "33") (name "Net-(C15-Pad2)") (class "Default")
      (node (ref "C15") (pin "2") (pinfunction "2_2") (pintype "passive"))
      (node (ref "R13") (pin "2") (pinfunction "2_2") (pintype "passive"))
      (node (ref "R14") (pin "1") (pinfunction "1_1") (pintype "passive"))
    )
    (net (code "34") (name "Net-(C16-Pad1)") (class "Default")
      (node (ref "C16") (pin "1") (pinfunction "1_1") (pintype "passive"))
      (node (ref "R13") (pin "1") (pinfunction "1_1") (pintype "passive"))
      (node (ref "R16") (pin "1") (pinfunction "1_1") (pintype "passive"))
      (node (ref "R17") (pin "2") (pinfunction "2_2") (pintype "passive"))
      (node (ref "R18") (pin "1") (pinfunction "1_1") (pintype "passive"))
    )
    (net (code "35") (name "Net-(C17-Pad1)") (class "Default")
      (node (ref "C17") (pin "1") (pinfunction "1_1") (pintype "passive"))
      (node (ref "R19") (pin "2") (pinfunction "2_2") (pintype "passive"))
      (node (ref "R20") (pin "1") (pinfunction "1_1") (pintype "passive"))
      (node (ref "R21") (pin "1") (pinfunction "1_1") (pintype "passive"))
    )
    (net (code "36") (name "Net-(C18-Pad1)") (class "Default")
      (node (ref "C18") (pin "1") (pinfunction "1_1") (pintype "passive"))
      (node (ref "R22") (pin "1") (pinfunction "1_1") (pintype "passive"))
      (node (ref "R23") (pin "1") (pinfunction "1_1") (pintype "passive"))
    )
    (net (code "37") (name "Net-(C18-Pad2)") (class "Default")
      (node (ref "C18") (pin "2") (pinfunction "2_2") (pintype "passive"))
      (node (ref "C20") (pin "2") (pinfunction "2_2") (pintype "passive"))
      (node (ref "R28") (pin "2") (pinfunction "2_2") (pintype "passive"))
    )
    (net (code "38") (name "Net-(C19-Pad1)") (class "Default")
      (node (ref "C19") (pin "1") (pinfunction "1_1") (pintype "passive"))
      (node (ref "R24") (pin "2") (pinfunction "2_2") (pintype "passive"))
      (node (ref "R25") (pin "2") (pinfunction "2_2") (pintype "passive"))
    )
    (net (code "39") (name "Net-(C19-Pad2)") (class "Default")
      (node (ref "C19") (pin "2") (pinfunction "2_2") (pintype "passive"))
      (node (ref "C21") (pin "1") (pinfunction "1_1") (pintype "passive"))
      (node (ref "R26") (pin "1") (pinfunction "1_1") (pintype "passive"))
    )
    (net (code "40") (name "Net-(C25-Pad2)") (class "Default")
      (node (ref "C25") (pin "2") (pinfunction "2_2") (pintype "passive"))
      (node (ref "R32") (pin "2") (pinfunction "2_2") (pintype "passive"))
    )
    (net (code "41") (name "Net-(C26-Pad2)") (class "Default")
      (node (ref "C26") (pin "2") (pinfunction "2_2") (pintype "passive"))
      (node (ref "R35") (pin "1") (pinfunction "1_1") (pintype "passive"))
    )
    (net (code "42") (name "Net-(D1-A)") (class "Default")
      (node (ref "D1") (pin "1") (pinfunction "A_1") (pintype "passive"))
      (node (ref "D2") (pin "2") (pinfunction "K_2") (pintype "passive"))
      (node (ref "L1") (pin "1") (pinfunction "1_1") (pintype "passive"))
      (node (ref "Q1") (pin "3") (pinfunction "S_3") (pintype "passive"))
      (node (ref "Q2") (pin "1") (pinfunction "D_1") (pintype "passive"))
    )
    (net (code "43") (name "Net-(D5-K)") (class "Default")
      (node (ref "C10") (pin "1") (pinfunction "1_1") (pintype "passive"))
      (node (ref "C9") (pin "1") (pinfunction "1_1") (pintype "passive"))
      (node (ref "D5") (pin "2") (pinfunction "K_2") (pintype "passive"))
      (node (ref "R7") (pin "1") (pinfunction "1_1") (pintype "passive"))
    )
    (net (code "44") (name "Net-(J1-CC1)") (class "Default")
      (node (ref "J1") (pin "A5") (pinfunction "CC1_A5") (pintype "bidirectional"))
      (node (ref "R3") (pin "1") (pinfunction "1_1") (pintype "passive"))
    )
    (net (code "45") (name "Net-(J1-CC2)") (class "Default")
      (node (ref "J1") (pin "B5") (pinfunction "CC2_B5") (pintype "bidirectional"))
      (node (ref "R2") (pin "1") (pinfunction "1_1") (pintype "passive"))
    )
    (net (code "46") (name "Net-(MSU1-VCAP)") (class "Default")
      (node (ref "C27") (pin "1") (pinfunction "1_1") (pintype "passive"))
      (node (ref "MSU1") (pin "8") (pinfunction "VCAP_8") (pintype "power_in"))
    )
    (net (code "47") (name "Net-(Q1-G)") (class "Default")
      (node (ref "Q1") (pin "2") (pinfunction "G_2") (pintype "passive"))
      (node (ref "Q4") (pin "2") (pinfunction "G_2") (pintype "passive"))
      (node (ref "R4") (pin "1") (pinfunction "1_1") (pintype "passive"))
      (node (ref "U2") (pin "1") (pinfunction "1OUT_1") (pintype "output"))
    )
    (net (code "48") (name "Net-(Q2-G)") (class "Default")
      (node (ref "Q2") (pin "2") (pinfunction "G_2") (pintype "passive"))
      (node (ref "Q3") (pin "2") (pinfunction "G_2") (pintype "passive"))
      (node (ref "R5") (pin "1") (pinfunction "1_1") (pintype "passive"))
      (node (ref "U2") (pin "7") (pinfunction "2OUT_7") (pintype "output"))
    )
    (net (code "49") (name "Net-(R29-Pad1)") (class "Default")
      (node (ref "R29") (pin "1") (pinfunction "1_1") (pintype "passive"))
      (node (ref "R30") (pin "1") (pinfunction "1_1") (pintype "passive"))
      (node (ref "R31") (pin "1") (pinfunction "1_1") (pintype "passive"))
    )
    (net (code "50") (name "Net-(U2-1IN-)") (class "Default")
      (node (ref "R4") (pin "2") (pinfunction "2_2") (pintype "passive"))
      (node (ref "U2") (pin "2") (pinfunction "1IN-_2") (pintype "input"))
    )
    (net (code "51") (name "Net-(U2-2IN-)") (class "Default")
      (node (ref "R5") (pin "2") (pinfunction "2_2") (pintype "passive"))
      (node (ref "U2") (pin "6") (pinfunction "2IN-_6") (pintype "input"))
    )
    (net (code "52") (name "unconnected-(J1-DN1-PadA7)") (class "Default")
      (node (ref "J1") (pin "A7") (pinfunction "DN1_A7") (pintype "bidirectional+no_connect"))
    )
    (net (code "53") (name "unconnected-(J1-DN2-PadB7)") (class "Default")
      (node (ref "J1") (pin "B7") (pinfunction "DN2_B7") (pintype "bidirectional+no_connect"))
    )
    (net (code "54") (name "unconnected-(J1-DP1-PadA6)") (class "Default")
      (node (ref "J1") (pin "A6") (pinfunction "DP1_A6") (pintype "bidirectional+no_connect"))
    )
    (net (code "55") (name "unconnected-(J1-DP2-PadB6)") (class "Default")
      (node (ref "J1") (pin "B6") (pinfunction "DP2_B6") (pintype "bidirectional+no_connect"))
    )
    (net (code "56") (name "unconnected-(J1-SBU1-PadA8)") (class "Default")
      (node (ref "J1") (pin "A8") (pinfunction "SBU1_A8") (pintype "bidirectional+no_connect"))
    )
    (net (code "57") (name "unconnected-(J1-SBU2-PadB8)") (class "Default")
      (node (ref "J1") (pin "B8") (pinfunction "SBU2_B8") (pintype "bidirectional+no_connect"))
    )
    (net (code "58") (name "unconnected-(J1-SHIELD-PadS1)") (class "Default")
      (node (ref "J1") (pin "S1") (pinfunction "SHIELD_S1") (pintype "passive+no_connect"))
    )
    (net (code "59") (name "unconnected-(J1-SHIELD-PadS2)") (class "Default")
      (node (ref "J1") (pin "S2") (pinfunction "SHIELD_S2") (pintype "passive+no_connect"))
    )
    (net (code "60") (name "unconnected-(J1-SHIELD-PadS3)") (class "Default")
      (node (ref "J1") (pin "S3") (pinfunction "SHIELD_S3") (pintype "passive+no_connect"))
    )
    (net (code "61") (name "unconnected-(J1-SHIELD-PadS4)") (class "Default")
      (node (ref "J1") (pin "S4") (pinfunction "SHIELD_S4") (pintype "passive+no_connect"))
    )
    (net (code "62") (name "unconnected-(MSU1-PB5-Pad11)") (class "Default")
      (node (ref "MSU1") (pin "11") (pinfunction "PB5_11") (pintype "bidirectional"))
    )
    (net (code "63") (name "unconnected-(MSU1-PC5-Pad15)") (class "Default")
      (node (ref "MSU1") (pin "15") (pinfunction "PC5_15") (pintype "bidirectional"))
    )
    (net (code "64") (name "unconnected-(MSU1-PC6-Pad16)") (class "Default")
      (node (ref "MSU1") (pin "16") (pinfunction "PC6_16") (pintype "bidirectional"))
    )
    (net (code "65") (name "unconnected-(MSU1-PC7-Pad17)") (class "Default")
      (node (ref "MSU1") (pin "17") (pinfunction "PC7_17") (pintype "bidirectional"))
    )
    (net (code "66") (name "unconnected-(MSU1-PD1-Pad18)") (class "Default")
      (node (ref "MSU1") (pin "18") (pinfunction "PD1_18") (pintype "bidirectional"))
    )
    (net (code "67") (name "unconnected-(MSU1-PD4-Pad1)") (class "Default")
      (node (ref "MSU1") (pin "1") (pinfunction "PD4_1") (pintype "bidirectional"))
    )
    (net (code "68") (name "unconnected-(MSU1-PD5-Pad2)") (class "Default")
      (node (ref "MSU1") (pin "2") (pinfunction "PD5_2") (pintype "bidirectional"))
    )
    (net (code "69") (name "unconnected-(MSU1-PD6-Pad3)") (class "Default")
      (node (ref "MSU1") (pin "3") (pinfunction "PD6_3") (pintype "bidirectional"))
    )
    (net (code "70") (name "unconnected-(U2-3IN+-Pad10)") (class "Default")
      (node (ref "U2") (pin "10") (pinfunction "3IN+_10") (pintype "input+no_connect"))
    )
    (net (code "71") (name "unconnected-(U2-3IN--Pad9)") (class "Default")
      (node (ref "U2") (pin "9") (pinfunction "3IN-_9") (pintype "input+no_connect"))
    )
    (net (code "72") (name "unconnected-(U2-3OUT-Pad8)") (class "Default")
      (node (ref "U2") (pin "8") (pinfunction "3OUT_8") (pintype "output+no_connect"))
    )
    (net (code "73") (name "unconnected-(U2-4IN+-Pad12)") (class "Default")
      (node (ref "U2") (pin "12") (pinfunction "4IN+_12") (pintype "input+no_connect"))
    )
    (net (code "74") (name "unconnected-(U2-4IN--Pad13)") (class "Default")
      (node (ref "U2") (pin "13") (pinfunction "4IN-_13") (pintype "input+no_connect"))
    )
    (net (code "75") (name "unconnected-(U2-4OUT-Pad14)") (class "Default")
      (node (ref "U2") (pin "14") (pinfunction "4OUT_14") (pintype "output+no_connect"))
    )
  )
)
